# SAMC21N_Xplained_Pro_dual_input_power_su.net
KiCad netlist of a schematic drawn in Altium Designer
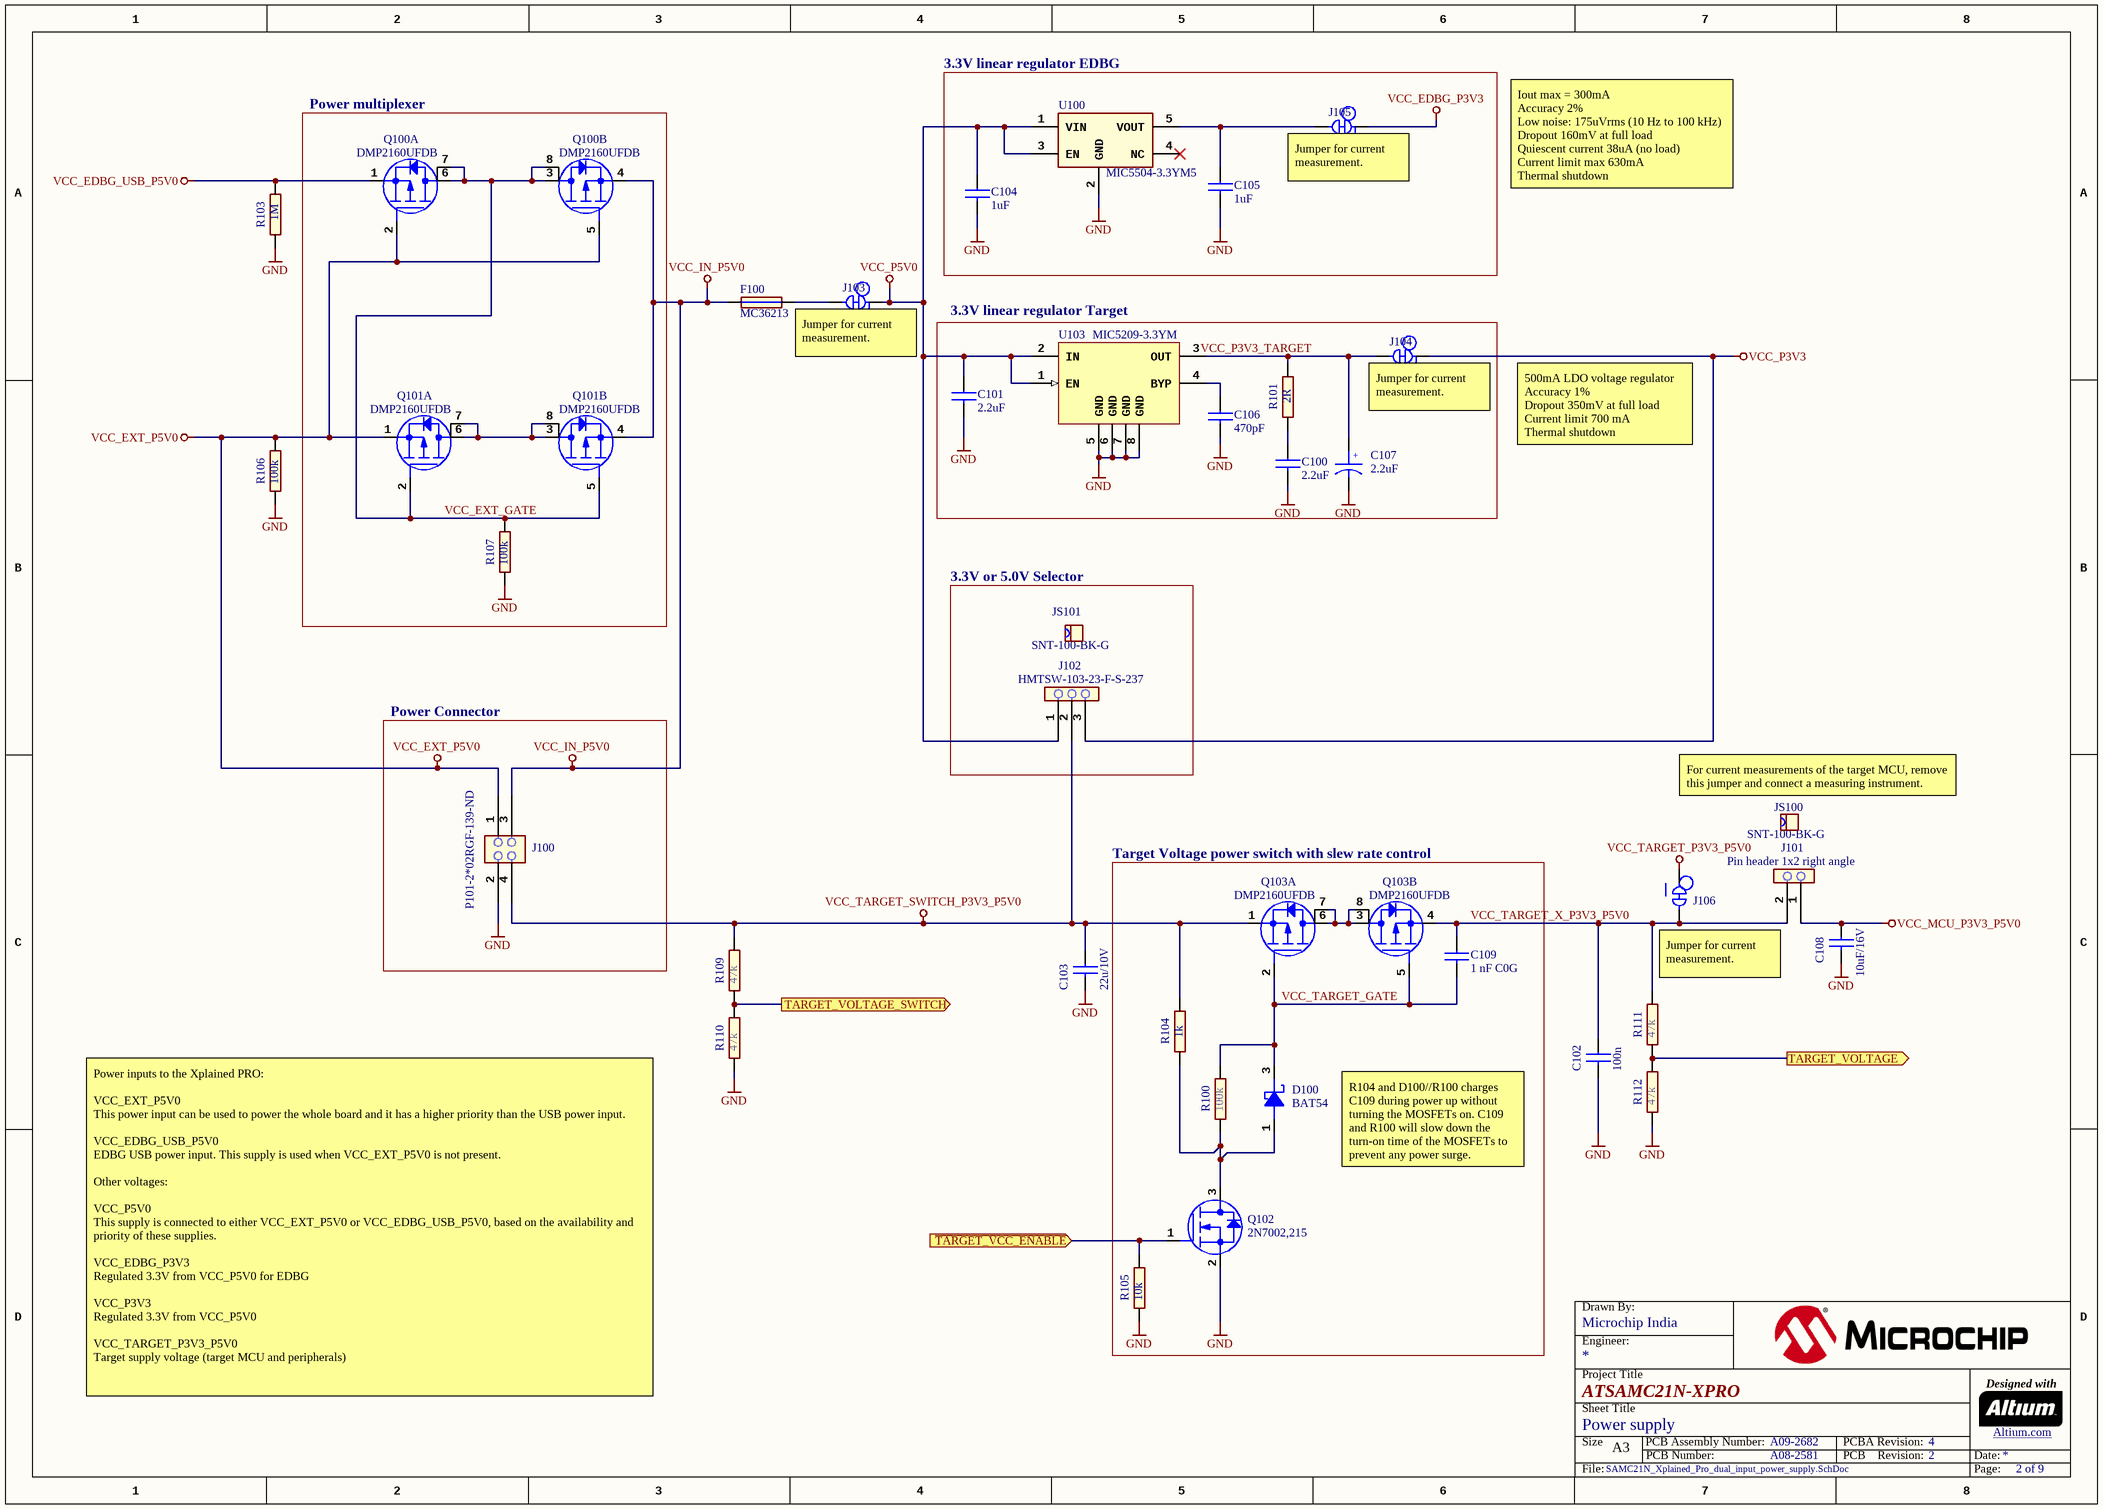
[diagram p0: SAMC21N_Xplained_Pro_dual_input_power_supply.SchDoc]

(export (version "E")
  (design (tool "Eeschema 10.0.6"))
  (components
    (comp (ref "C100")
      (value "2.2uF")
      (footprint "AP1-00096")
      (description "Ceramic capacitor, SMD 0603, X7R, 10V, 10%")
      (fields
        (field (name "TOLERANCE") "10%")
        (field (name "MANUFACTURER") "Murata")
        (field (name "VERIFIED BY") "Lars Helge Mo")
      )
      (libsource (lib "AltiumDbLib") (part "CAP-NONPOL"))
    )
    (comp (ref "C101")
      (value "2.2uF")
      (footprint "AP1-00096")
      (description "Ceramic capacitor, SMD 0603, X7R, 10V, 10%")
      (fields
        (field (name "TOLERANCE") "10%")
        (field (name "MANUFACTURER") "Murata")
        (field (name "VERIFIED BY") "Lars Helge Mo")
      )
      (libsource (lib "AltiumDbLib") (part "CAP-NONPOL"))
    )
    (comp (ref "C102")
      (value "100n")
      (footprint "AP1-00001")
      (description "Ceramic capacitor, SMD 0402, X7R, 16V, +/-10%")
      (fields
        (field (name "TOLERANCE") "16V, +/-10%")
        (field (name "MANUFACTURER") "Kemet")
        (field (name "VERIFIED BY") "Lars Helge Mo")
      )
      (libsource (lib "AltiumDbLib") (part "CAP-NONPOL"))
    )
    (comp (ref "C103")
      (value "22u/10V")
      (footprint "AP1-00003")
      (description "Ceramic capacitor, SMD 0805, X5R, 10V, Â±20%")
      (fields
        (field (name "MANUFACTURER") "tdk")
        (field (name "MPN") "C2012X5R1A226M/0.85")
        (field (name "VERIFIED BY") "Lars Helge Mo")
      )
      (libsource (lib "AltiumDbLib") (part "CAP-NONPOL"))
    )
    (comp (ref "C104")
      (value "1uF")
      (footprint "AP1-00001")
      (description "Ceramic capacitor, SMD 0402, X5R, 10V, 10%")
      (fields
        (field (name "TOLERANCE") "10%")
        (field (name "MANUFACTURER") "Murata")
        (field (name "VERIFIED BY") "Lars Helge Mo")
      )
      (libsource (lib "AltiumDbLib") (part "CAP-NONPOL"))
    )
    (comp (ref "C105")
      (value "1uF")
      (footprint "AP1-00001")
      (description "Ceramic capacitor, SMD 0402, X5R, 10V, 10%")
      (fields
        (field (name "TOLERANCE") "10%")
        (field (name "MANUFACTURER") "Murata")
        (field (name "VERIFIED BY") "Lars Helge Mo")
      )
      (libsource (lib "AltiumDbLib") (part "CAP-NONPOL"))
    )
    (comp (ref "C106")
      (value "470pF")
      (footprint "AP1-00001")
      (description "Ceramic capacitor, SMD 0402, NP0, 50V, +/-5%")
      (fields
        (field (name "TOLERANCE") "50V, +/-5%")
        (field (name "MANUFACTURER") "Murata")
        (field (name "VERIFIED BY") "Lars Helge Mo")
      )
      (libsource (lib "AltiumDbLib") (part "CAP-NONPOL"))
    )
    (comp (ref "C107")
      (value "2.2uF")
      (footprint "AP1-00036")
      (description "Capacitor Tantalum 10V 2.2uF 10% ESR = 6 ohm")
      (fields
        (field (name "TOLERANCE") "±10%")
        (field (name "MANUFACTURER") "Kemet")
        (field (name "VERIFIED BY") "Ketil Skjerve")
      )
      (libsource (lib "AltiumDbLib") (part "CAP-POL"))
    )
    (comp (ref "C108")
      (value "10uF/16V")
      (footprint "AP1-00039")
      (description "Ceramic capacitor, SMD 0603, X5R, 16V, 10UF ± 20% (High Density)")
      (fields
        (field (name "TOLERANCE") "­± 20%")
        (field (name "MANUFACTURER") "Taiyo Yuden")
        (field (name "VERIFIED BY") "Lars Helge Mo")
      )
      (libsource (lib "AltiumDbLib") (part "CAP-NONPOL"))
    )
    (comp (ref "C109")
      (value "1 nF C0G")
      (footprint "AP1-00053")
      (description "Ceramic capacitor, SMD 0402, C0G, 50V, +/-5%")
      (fields
        (field (name "TOLERANCE") "5%")
        (field (name "MANUFACTURER") "Murata")
        (field (name "VERIFIED BY") "Lars Helge Mo")
      )
      (libsource (lib "AltiumDbLib") (part "CAP-NONPOL"))
    )
    (comp (ref "D100")
      (value "BAT54")
      (footprint "AP4-00007")
      (fields
        (field (name "MANUFACTURER") "Philips")
        (field (name "Comment") "SCHOTTKY_SMD_31")
        (field (name "VERIFIED BY") "Ketil Skjerve")
      )
      (libsource (lib "AltiumDbLib") (part "SCHOTTKY_SMD_31"))
    )
    (comp (ref "F100")
      (value "MC36213")
      (footprint "AP2-00002")
      (description "Resetable PTC fuse, Ih = 0.5A, It = 1.0A, 0805 package")
      (fields
        (field (name "MANUFACTURER") "Multicomp")
        (field (name "Comment") "Farnell no: 1861197")
        (field (name "VERIFIED BY") "Ketil Skjerve")
      )
      (libsource (lib "AltiumDbLib") (part "FUSE"))
    )
    (comp (ref "J100")
      (value "P101-2*02RGF-139-ND")
      (footprint "AP8-00628")
      (description "Pin header, 2x2, Right Angle, 2.54mm, THT, Pin In Paste")
      (fields (field (name "Comment") "HEADER 2x2") (field (name "VERIFIED BY") "Lars Helge Mo"))
      (libsource (lib "AltiumDbLib") (part "HEADER 2x2"))
    )
    (comp (ref "J101")
      (value "Pin header 1x2 right angle")
      (footprint "AP8-00367")
      (description "1x2 pin header, right angle, 2.54 mm pitch, through-hole")
      (fields
        (field (name "MANUFACTURER") "Pro-data International Corp")
        (field (name "MPN") "2213R-2G")
        (field (name "VERIFIED BY") "Lars Helge")
      )
      (libsource (lib "AltiumDbLib") (part "HEADER 1x2"))
    )
    (comp (ref "J102")
      (value "HMTSW-103-23-F-S-237")
      (footprint "AP8-00745")
      (description "1x3 pin header, 2.54mm pitch, Pin-in-Paste THM, 1mm hole")
      (fields
        (field (name "MANUFACTURER") "SAMTEC")
        (field (name "Comment") "Same as A08-1614 but with 1mm hole for optimal reflow soldering (no misalignment of the component)")
        (field (name "VERIFIED BY") "Lars Helge Mo")
      )
      (libsource (lib "AltiumDbLib") (part "HEADER 1x3"))
    )
    (comp (ref "J103")
      (value "SMD-STRAP_CLOSED")
      (footprint "AP9-00044")
      (description "Default closed SMD strap, 0603 size")
      (libsource (lib "AltiumDbLib") (part "SMD-STRAP_CLOSED"))
    )
    (comp (ref "J104")
      (value "SMD-STRAP_CLOSED")
      (footprint "AP9-00044")
      (description "Default closed SMD strap, 0603 size")
      (libsource (lib "AltiumDbLib") (part "SMD-STRAP_CLOSED"))
    )
    (comp (ref "J105")
      (value "SMD-STRAP_CLOSED")
      (footprint "AP9-00044")
      (description "Default closed SMD strap, 0603 size")
      (libsource (lib "AltiumDbLib") (part "SMD-STRAP_CLOSED"))
    )
    (comp (ref "J106")
      (value "SMD-STRAP_CLOSED")
      (footprint "AP9-00044")
      (description "Default closed SMD strap, 0603 size")
      (libsource (lib "AltiumDbLib") (part "SMD-STRAP_CLOSED"))
    )
    (comp (ref "JS100")
      (value "SNT-100-BK-G")
      (footprint "AP8-00525")
      (description "Jumper cap for 2.54mm pinheader")
      (fields
        (field (name "MANUFACTURER") "SAMTEC")
        (field (name "Comment") "To be used by request from ESCATEC")
        (field (name "VERIFIED BY") "Lars Helge Mo")
      )
      (libsource (lib "AltiumDbLib") (part "JUMPER_CAP"))
    )
    (comp (ref "JS101")
      (value "SNT-100-BK-G")
      (footprint "AP8-00525")
      (description "Jumper cap for 2.54mm pinheader")
      (fields
        (field (name "MANUFACTURER") "SAMTEC")
        (field (name "Comment") "To be used by request from ESCATEC")
        (field (name "VERIFIED BY") "Lars Helge Mo")
      )
      (libsource (lib "AltiumDbLib") (part "JUMPER_CAP"))
    )
    (comp (ref "Q100")
      (value "DMP2160UFDB")
      (footprint "AP5-00047")
      (description "MOSFET 20V 3.8A DUAL P-CHAN, Rds 70 mOhms, Vgs 12V, Vds -20")
      (fields (field (name "MANUFACTURER") "Diodes Incorporated") (field (name "MPN") "DMP2160UFDB-7"))
      (libsource (lib "AltiumDbLib") (part "MOSFET_DUAL_P_S1G1D2S2G2D1D1D2"))
    )
    (comp (ref "Q101")
      (value "DMP2160UFDB")
      (footprint "AP5-00047")
      (description "MOSFET 20V 3.8A DUAL P-CHAN, Rds 70 mOhms, Vgs 12V, Vds -20")
      (fields (field (name "MANUFACTURER") "Diodes Incorporated") (field (name "MPN") "DMP2160UFDB-7"))
      (libsource (lib "AltiumDbLib") (part "MOSFET_DUAL_P_S1G1D2S2G2D1D1D2"))
    )
    (comp (ref "Q102")
      (value "2N7002,215")
      (footprint "AP5-00002")
      (description "N-Channel MOSFET. 60V, 0.300A continuous, 1.2A Peak. RDS(ON) = 3.8Ohm@VGS=4.5V, VGS(th)<2.5V")
      (fields (field (name "MANUFACTURER") "NXP") (field (name "Comment") "MOSFET_N_GSD"))
      (libsource (lib "AltiumDbLib") (part "MOSFET_N_GSD"))
    )
    (comp (ref "Q103")
      (value "DMP2160UFDB")
      (footprint "AP5-00047")
      (description "MOSFET 20V 3.8A DUAL P-CHAN, Rds 70 mOhms, Vgs 12V, Vds -20")
      (fields (field (name "MANUFACTURER") "Diodes Incorporated") (field (name "MPN") "DMP2160UFDB-7"))
      (libsource (lib "AltiumDbLib") (part "MOSFET_DUAL_P_S1G1D2S2G2D1D1D2"))
    )
    (comp (ref "R100")
      (value "100k")
      (footprint "AP2-00000")
      (description "Thick film resistor, SMD 0402, 1/16W, 1%")
      (fields
        (field (name "TOLERANCE") "1 %")
        (field (name "Comment") "R2")
        (field (name "VERIFIED BY") "Lars Helge Mo")
      )
      (libsource (lib "AltiumDbLib") (part "R2"))
    )
    (comp (ref "R101")
      (value "2R")
      (footprint "AP2-00000")
      (description "RES SMD 2 OHM 1% 1/16W 0402")
      (fields (field (name "Comment") "R2") (field (name "VERIFIED BY") "Lars Helge Mo"))
      (libsource (lib "AltiumDbLib") (part "R2"))
    )
    (comp (ref "R103")
      (value "1M")
      (footprint "AP2-00000")
      (description "Thick film resistor, SMD 0402, 1/16W, 1%")
      (fields
        (field (name "TOLERANCE") "1 %")
        (field (name "Comment") "R2")
        (field (name "VERIFIED BY") "Lars Helge Mo")
      )
      (libsource (lib "AltiumDbLib") (part "R2"))
    )
    (comp (ref "R104")
      (value "1k")
      (footprint "AP2-00000")
      (description "Thick film resistor, SMD 0402, 1/16W, 1%")
      (fields
        (field (name "TOLERANCE") "1 %")
        (field (name "Comment") "R2")
        (field (name "VERIFIED BY") "Lars Helge Mo")
      )
      (libsource (lib "AltiumDbLib") (part "R2"))
    )
    (comp (ref "R105")
      (value "10k")
      (footprint "AP2-00000")
      (description "Thick film resistor, SMD 0402, 1/16W, 1%")
      (fields
        (field (name "TOLERANCE") "1 %")
        (field (name "MANUFACTURER") "vishay")
        (field (name "VERIFIED BY") "Lars Helge Mo")
      )
      (libsource (lib "AltiumDbLib") (part "R2"))
    )
    (comp (ref "R106")
      (value "100k")
      (footprint "AP2-00000")
      (description "Thick film resistor, SMD 0402, 1/16W, 1%")
      (fields
        (field (name "TOLERANCE") "1 %")
        (field (name "Comment") "R2")
        (field (name "VERIFIED BY") "Lars Helge Mo")
      )
      (libsource (lib "AltiumDbLib") (part "R2"))
    )
    (comp (ref "R107")
      (value "100k")
      (footprint "AP2-00000")
      (description "Thick film resistor, SMD 0402, 1/16W, 1%")
      (fields
        (field (name "TOLERANCE") "1 %")
        (field (name "Comment") "R2")
        (field (name "VERIFIED BY") "Lars Helge Mo")
      )
      (libsource (lib "AltiumDbLib") (part "R2"))
    )
    (comp (ref "R109")
      (value "47k")
      (footprint "AP2-00000")
      (description "Thick film resistor, SMD 0402, 1/16W, 1%")
      (fields
        (field (name "TOLERANCE") "1 %")
        (field (name "Comment") "R2")
        (field (name "VERIFIED BY") "Lars Helge Mo")
      )
      (libsource (lib "") (part "R2_1"))
    )
    (comp (ref "R110")
      (value "47k")
      (footprint "AP2-00000")
      (description "Thick film resistor, SMD 0402, 1/16W, 1%")
      (fields
        (field (name "TOLERANCE") "1 %")
        (field (name "Comment") "R2")
        (field (name "VERIFIED BY") "Lars Helge Mo")
      )
      (libsource (lib "") (part "R2_1"))
    )
    (comp (ref "R111")
      (value "47k")
      (footprint "AP2-00000")
      (description "Thick film resistor, SMD 0402, 1/16W, 1%")
      (fields
        (field (name "TOLERANCE") "1 %")
        (field (name "Comment") "R2")
        (field (name "VERIFIED BY") "Lars Helge Mo")
      )
      (libsource (lib "") (part "R2_1"))
    )
    (comp (ref "R112")
      (value "47k")
      (footprint "AP2-00000")
      (description "Thick film resistor, SMD 0402, 1/16W, 1%")
      (fields
        (field (name "TOLERANCE") "1 %")
        (field (name "Comment") "R2")
        (field (name "VERIFIED BY") "Lars Helge Mo")
      )
      (libsource (lib "") (part "R2_1"))
    )
    (comp (ref "U100")
      (value "MIC5504-3.3YM5")
      (footprint "AP6-00087")
      (description "LDO 3.3V 0.3A SOT-23-5")
      (fields
        (field (name "MANUFACTURER") "Microchip")
        (field (name "MPN") "MIC5504-3.3YM5-TR")
        (field (name "VERIFIED BY") "*")
      )
      (libsource (lib "AltiumDbLib") (part "MIC5504"))
    )
    (comp (ref "U103")
      (value "MIC5209-3.3YM")
      (footprint "AP6-00000")
      (description "Fixed 3.3V, 500mA Low-Noise LDO Regulator, SOIC-8")
      (fields (field (name "MANUFACTURER") "Microchip"))
      (libsource (lib "AltiumDbLib") (part "MIC5209"))
    )
  )
  (nets
    (net (code "1") (name "/TARGET_VOLTAGE") (class "Default")
      (node (ref "R111") (pin "1") (pinfunction "1_1") (pintype "passive"))
      (node (ref "R112") (pin "2") (pinfunction "2_2") (pintype "passive"))
    )
    (net (code "2") (name "/TARGET_VOLTAGE_SWITCH") (class "Default")
      (node (ref "R109") (pin "1") (pinfunction "1_1") (pintype "passive"))
      (node (ref "R110") (pin "2") (pinfunction "2_2") (pintype "passive"))
    )
    (net (code "3") (name "/VCC_EXT_GATE") (class "Default")
      (node (ref "Q100") (pin "3") (pinfunction "D2_3") (pintype "passive"))
      (node (ref "Q100") (pin "6") (pinfunction "D1_6") (pintype "passive"))
      (node (ref "Q100") (pin "7") (pinfunction "D1_PAD_7") (pintype "passive"))
      (node (ref "Q100") (pin "8") (pinfunction "D2_PAD_8") (pintype "passive"))
      (node (ref "Q101") (pin "2") (pinfunction "G1_2") (pintype "passive"))
      (node (ref "Q101") (pin "5") (pinfunction "G2_5") (pintype "passive"))
      (node (ref "R107") (pin "2") (pinfunction "2_2") (pintype "passive"))
    )
    (net (code "5") (name "/VCC_TARGET_GATE") (class "Default")
      (node (ref "C109") (pin "2") (pinfunction "2_2") (pintype "passive"))
      (node (ref "D100") (pin "3") (pinfunction "CATHODE_3") (pintype "passive"))
      (node (ref "Q103") (pin "2") (pinfunction "G1_2") (pintype "passive"))
      (node (ref "Q103") (pin "5") (pinfunction "G2_5") (pintype "passive"))
      (node (ref "R100") (pin "2") (pinfunction "2_2") (pintype "passive"))
    )
    (net (code "6") (name "/VCC_TARGET_X_P3V3_P5V0") (class "Default")
      (node (ref "C102") (pin "1") (pinfunction "1_1") (pintype "passive"))
      (node (ref "C109") (pin "1") (pinfunction "1_1") (pintype "passive"))
      (node (ref "J101") (pin "2") (pinfunction "2_2") (pintype "passive"))
      (node (ref "J106") (pin "2") (pinfunction "2_2") (pintype "passive"))
      (node (ref "Q103") (pin "4") (pinfunction "S2_4") (pintype "passive"))
      (node (ref "R111") (pin "2") (pinfunction "2_2") (pintype "passive"))
    )
    (net (code "7") (name "/~{TARGET_VCC_ENABLE}") (class "Default")
      (node (ref "Q102") (pin "1") (pinfunction "G_1") (pintype "passive"))
      (node (ref "R105") (pin "2") (pinfunction "2_2") (pintype "passive"))
    )
    (net (code "8") (name "GND") (class "Default")
      (node (ref "C100") (pin "2") (pinfunction "2_2") (pintype "passive"))
      (node (ref "C101") (pin "2") (pinfunction "2_2") (pintype "passive"))
      (node (ref "C102") (pin "2") (pinfunction "2_2") (pintype "passive"))
      (node (ref "C103") (pin "2") (pinfunction "2_2") (pintype "passive"))
      (node (ref "C104") (pin "2") (pinfunction "2_2") (pintype "passive"))
      (node (ref "C105") (pin "2") (pinfunction "2_2") (pintype "passive"))
      (node (ref "C106") (pin "2") (pinfunction "2_2") (pintype "passive"))
      (node (ref "C107") (pin "2") (pinfunction "2_2") (pintype "passive"))
      (node (ref "C108") (pin "2") (pinfunction "2_2") (pintype "passive"))
      (node (ref "J100") (pin "2") (pinfunction "2_2") (pintype "passive"))
      (node (ref "Q102") (pin "2") (pinfunction "S_2") (pintype "passive"))
      (node (ref "R103") (pin "1") (pinfunction "1_1") (pintype "passive"))
      (node (ref "R105") (pin "1") (pinfunction "1_1") (pintype "passive"))
      (node (ref "R106") (pin "1") (pinfunction "1_1") (pintype "passive"))
      (node (ref "R107") (pin "1") (pinfunction "1_1") (pintype "passive"))
      (node (ref "R110") (pin "1") (pinfunction "1_1") (pintype "passive"))
      (node (ref "R112") (pin "1") (pinfunction "1_1") (pintype "passive"))
      (node (ref "U100") (pin "2") (pinfunction "GND_2") (pintype "power_in"))
      (node (ref "U103") (pin "5") (pinfunction "GND_5") (pintype "power_in"))
      (node (ref "U103") (pin "6") (pinfunction "GND_6") (pintype "power_in"))
      (node (ref "U103") (pin "7") (pinfunction "GND_7") (pintype "power_in"))
      (node (ref "U103") (pin "8") (pinfunction "GND_8") (pintype "power_in"))
    )
    (net (code "9") (name "Net-(C100-Pad1)") (class "Default")
      (node (ref "C100") (pin "1") (pinfunction "1_1") (pintype "passive"))
      (node (ref "R101") (pin "1") (pinfunction "1_1") (pintype "passive"))
    )
    (net (code "10") (name "Net-(D100-ANODE)") (class "Default")
      (node (ref "D100") (pin "1") (pinfunction "ANODE_1") (pintype "passive"))
      (node (ref "Q102") (pin "3") (pinfunction "D_3") (pintype "passive"))
      (node (ref "R100") (pin "1") (pinfunction "1_1") (pintype "passive"))
      (node (ref "R104") (pin "1") (pinfunction "1_1") (pintype "passive"))
    )
    (net (code "11") (name "Net-(F100-Pad2)") (class "Default")
      (node (ref "F100") (pin "2") (pinfunction "2_2") (pintype "passive"))
      (node (ref "J103") (pin "2") (pinfunction "2_2") (pintype "passive"))
    )
    (net (code "12") (name "Net-(Q101A-D1)") (class "Default")
      (node (ref "Q101") (pin "3") (pinfunction "D2_3") (pintype "passive"))
      (node (ref "Q101") (pin "6") (pinfunction "D1_6") (pintype "passive"))
      (node (ref "Q101") (pin "7") (pinfunction "D1_PAD_7") (pintype "passive"))
      (node (ref "Q101") (pin "8") (pinfunction "D2_PAD_8") (pintype "passive"))
    )
    (net (code "13") (name "Net-(Q103A-D1)") (class "Default")
      (node (ref "Q103") (pin "3") (pinfunction "D2_3") (pintype "passive"))
      (node (ref "Q103") (pin "6") (pinfunction "D1_6") (pintype "passive"))
      (node (ref "Q103") (pin "7") (pinfunction "D1_PAD_7") (pintype "passive"))
      (node (ref "Q103") (pin "8") (pinfunction "D2_PAD_8") (pintype "passive"))
    )
    (net (code "14") (name "Net-(U100-VOUT)") (class "Default")
      (node (ref "C105") (pin "1") (pinfunction "1_1") (pintype "passive"))
      (node (ref "J105") (pin "2") (pinfunction "2_2") (pintype "passive"))
      (node (ref "U100") (pin "5") (pinfunction "VOUT_5") (pintype "power_in"))
    )
    (net (code "15") (name "Net-(U103-BYP)") (class "Default")
      (node (ref "C106") (pin "1") (pinfunction "1_1") (pintype "passive"))
      (node (ref "U103") (pin "4") (pinfunction "BYP_4") (pintype "power_in"))
    )
    (net (code "16") (name "Net-(U103-OUT)") (class "Default")
      (node (ref "C107") (pin "1") (pinfunction "1_1") (pintype "passive"))
      (node (ref "J104") (pin "2") (pinfunction "2_2") (pintype "passive"))
      (node (ref "R101") (pin "2") (pinfunction "2_2") (pintype "passive"))
      (node (ref "U103") (pin "3") (pinfunction "OUT_3") (pintype "power_in"))
    )
    (net (code "17") (name "VCC_EDBG_P3V3") (class "Default")
      (node (ref "J105") (pin "1") (pinfunction "1_1") (pintype "passive"))
    )
    (net (code "18") (name "VCC_EDBG_USB_P5V0") (class "Default")
      (node (ref "Q100") (pin "1") (pinfunction "S1_1") (pintype "passive"))
      (node (ref "R103") (pin "2") (pinfunction "2_2") (pintype "passive"))
    )
    (net (code "19") (name "VCC_EXT_P5V0") (class "Default")
      (node (ref "J100") (pin "1") (pinfunction "1_1") (pintype "passive"))
      (node (ref "Q100") (pin "2") (pinfunction "G1_2") (pintype "passive"))
      (node (ref "Q100") (pin "5") (pinfunction "G2_5") (pintype "passive"))
      (node (ref "Q101") (pin "1") (pinfunction "S1_1") (pintype "passive"))
      (node (ref "R106") (pin "2") (pinfunction "2_2") (pintype "passive"))
    )
    (net (code "20") (name "VCC_IN_P5V0") (class "Default")
      (node (ref "F100") (pin "1") (pinfunction "1_1") (pintype "passive"))
      (node (ref "J100") (pin "3") (pinfunction "3_3") (pintype "passive"))
      (node (ref "Q100") (pin "4") (pinfunction "S2_4") (pintype "passive"))
      (node (ref "Q101") (pin "4") (pinfunction "S2_4") (pintype "passive"))
    )
    (net (code "21") (name "VCC_MCU_P3V3_P5V0") (class "Default")
      (node (ref "C108") (pin "1") (pinfunction "1_1") (pintype "passive"))
      (node (ref "J101") (pin "1") (pinfunction "1_1") (pintype "passive"))
    )
    (net (code "22") (name "VCC_P3V3") (class "Default")
      (node (ref "J102") (pin "3") (pinfunction "3_3") (pintype "passive"))
      (node (ref "J104") (pin "1") (pinfunction "1_1") (pintype "passive"))
    )
    (net (code "23") (name "VCC_P5V0") (class "Default")
      (node (ref "C101") (pin "1") (pinfunction "1_1") (pintype "passive"))
      (node (ref "C104") (pin "1") (pinfunction "1_1") (pintype "passive"))
      (node (ref "J102") (pin "1") (pinfunction "1_1") (pintype "passive"))
      (node (ref "J103") (pin "1") (pinfunction "1_1") (pintype "passive"))
      (node (ref "U100") (pin "1") (pinfunction "VIN_1") (pintype "power_in"))
      (node (ref "U100") (pin "3") (pinfunction "EN_3") (pintype "passive"))
      (node (ref "U103") (pin "1") (pinfunction "EN_1") (pintype "input"))
      (node (ref "U103") (pin "2") (pinfunction "IN_2") (pintype "power_in"))
    )
    (net (code "24") (name "VCC_TARGET_P3V3_P5V0") (class "Default")
      (node (ref "J106") (pin "1") (pinfunction "1_1") (pintype "passive"))
    )
    (net (code "25") (name "VCC_TARGET_SWITCH_P3V3_P5V0") (class "Default")
      (node (ref "C103") (pin "1") (pinfunction "1_1") (pintype "passive"))
      (node (ref "J100") (pin "4") (pinfunction "4_4") (pintype "passive"))
      (node (ref "J102") (pin "2") (pinfunction "2_2") (pintype "passive"))
      (node (ref "Q103") (pin "1") (pinfunction "S1_1") (pintype "passive"))
      (node (ref "R104") (pin "2") (pinfunction "2_2") (pintype "passive"))
      (node (ref "R109") (pin "2") (pinfunction "2_2") (pintype "passive"))
    )
    (net (code "26") (name "unconnected-(U100-NC-Pad4)") (class "Default")
      (node (ref "U100") (pin "4") (pinfunction "NC_4") (pintype "passive+no_connect"))
    )
  )
)
